# circuitPendulumBrushes.net
KiCad netlist of a schematic drawn in EAGLE
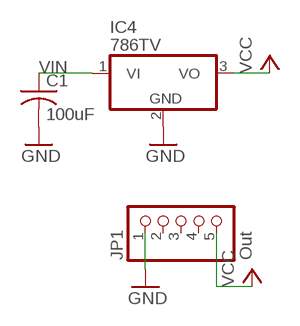
[diagram p0: schematic, sheet 1]

(export (version "E")
  (design (tool "Eeschema 10.0.6"))
  (components
    (comp (ref "C1")
      (value "100uF")
      (footprint "eagle-import:C050-045X075")
      (libsource (lib "eagle-import") (part "C-US050-045X075"))
    )
    (comp (ref "IC4")
      (value "786TV")
      (footprint "eagle-import:TO220V")
      (libsource (lib "eagle-import") (part "78TV6"))
    )
    (comp (ref "JP1")
      (value "Out")
      (footprint "eagle-import:1_05X2MM")
      (libsource (lib "eagle-import") (part "PINHD-1X55X2MM"))
    )
  )
  (nets
    (net (code "1") (name "/VIN") (class "Default")
      (node (ref "C1") (pin "1") (pinfunction "1_1") (pintype "passive"))
      (node (ref "IC4") (pin "1") (pinfunction "VI_1") (pintype "input"))
    )
    (net (code "2") (name "GND") (class "Default")
      (node (ref "C1") (pin "2") (pinfunction "2_2") (pintype "passive"))
      (node (ref "IC4") (pin "2") (pinfunction "GND_2") (pintype "passive"))
      (node (ref "JP1") (pin "1") (pinfunction "1_1") (pintype "passive"))
    )
    (net (code "3") (name "VCC") (class "Default")
      (node (ref "IC4") (pin "3") (pinfunction "VO_3") (pintype "passive"))
      (node (ref "JP1") (pin "5") (pinfunction "5_5") (pintype "passive"))
    )
    (net (code "4") (name "unconnected-(JP1-Pad2)") (class "Default")
      (node (ref "JP1") (pin "2") (pinfunction "2_2") (pintype "passive"))
    )
    (net (code "5") (name "unconnected-(JP1-Pad3)") (class "Default")
      (node (ref "JP1") (pin "3") (pinfunction "3_3") (pintype "passive"))
    )
    (net (code "6") (name "unconnected-(JP1-Pad4)") (class "Default")
      (node (ref "JP1") (pin "4") (pinfunction "4_4") (pintype "passive"))
    )
  )
)
